# Front_left_lamp_v2.net
KiCad netlist of a schematic drawn in EAGLE
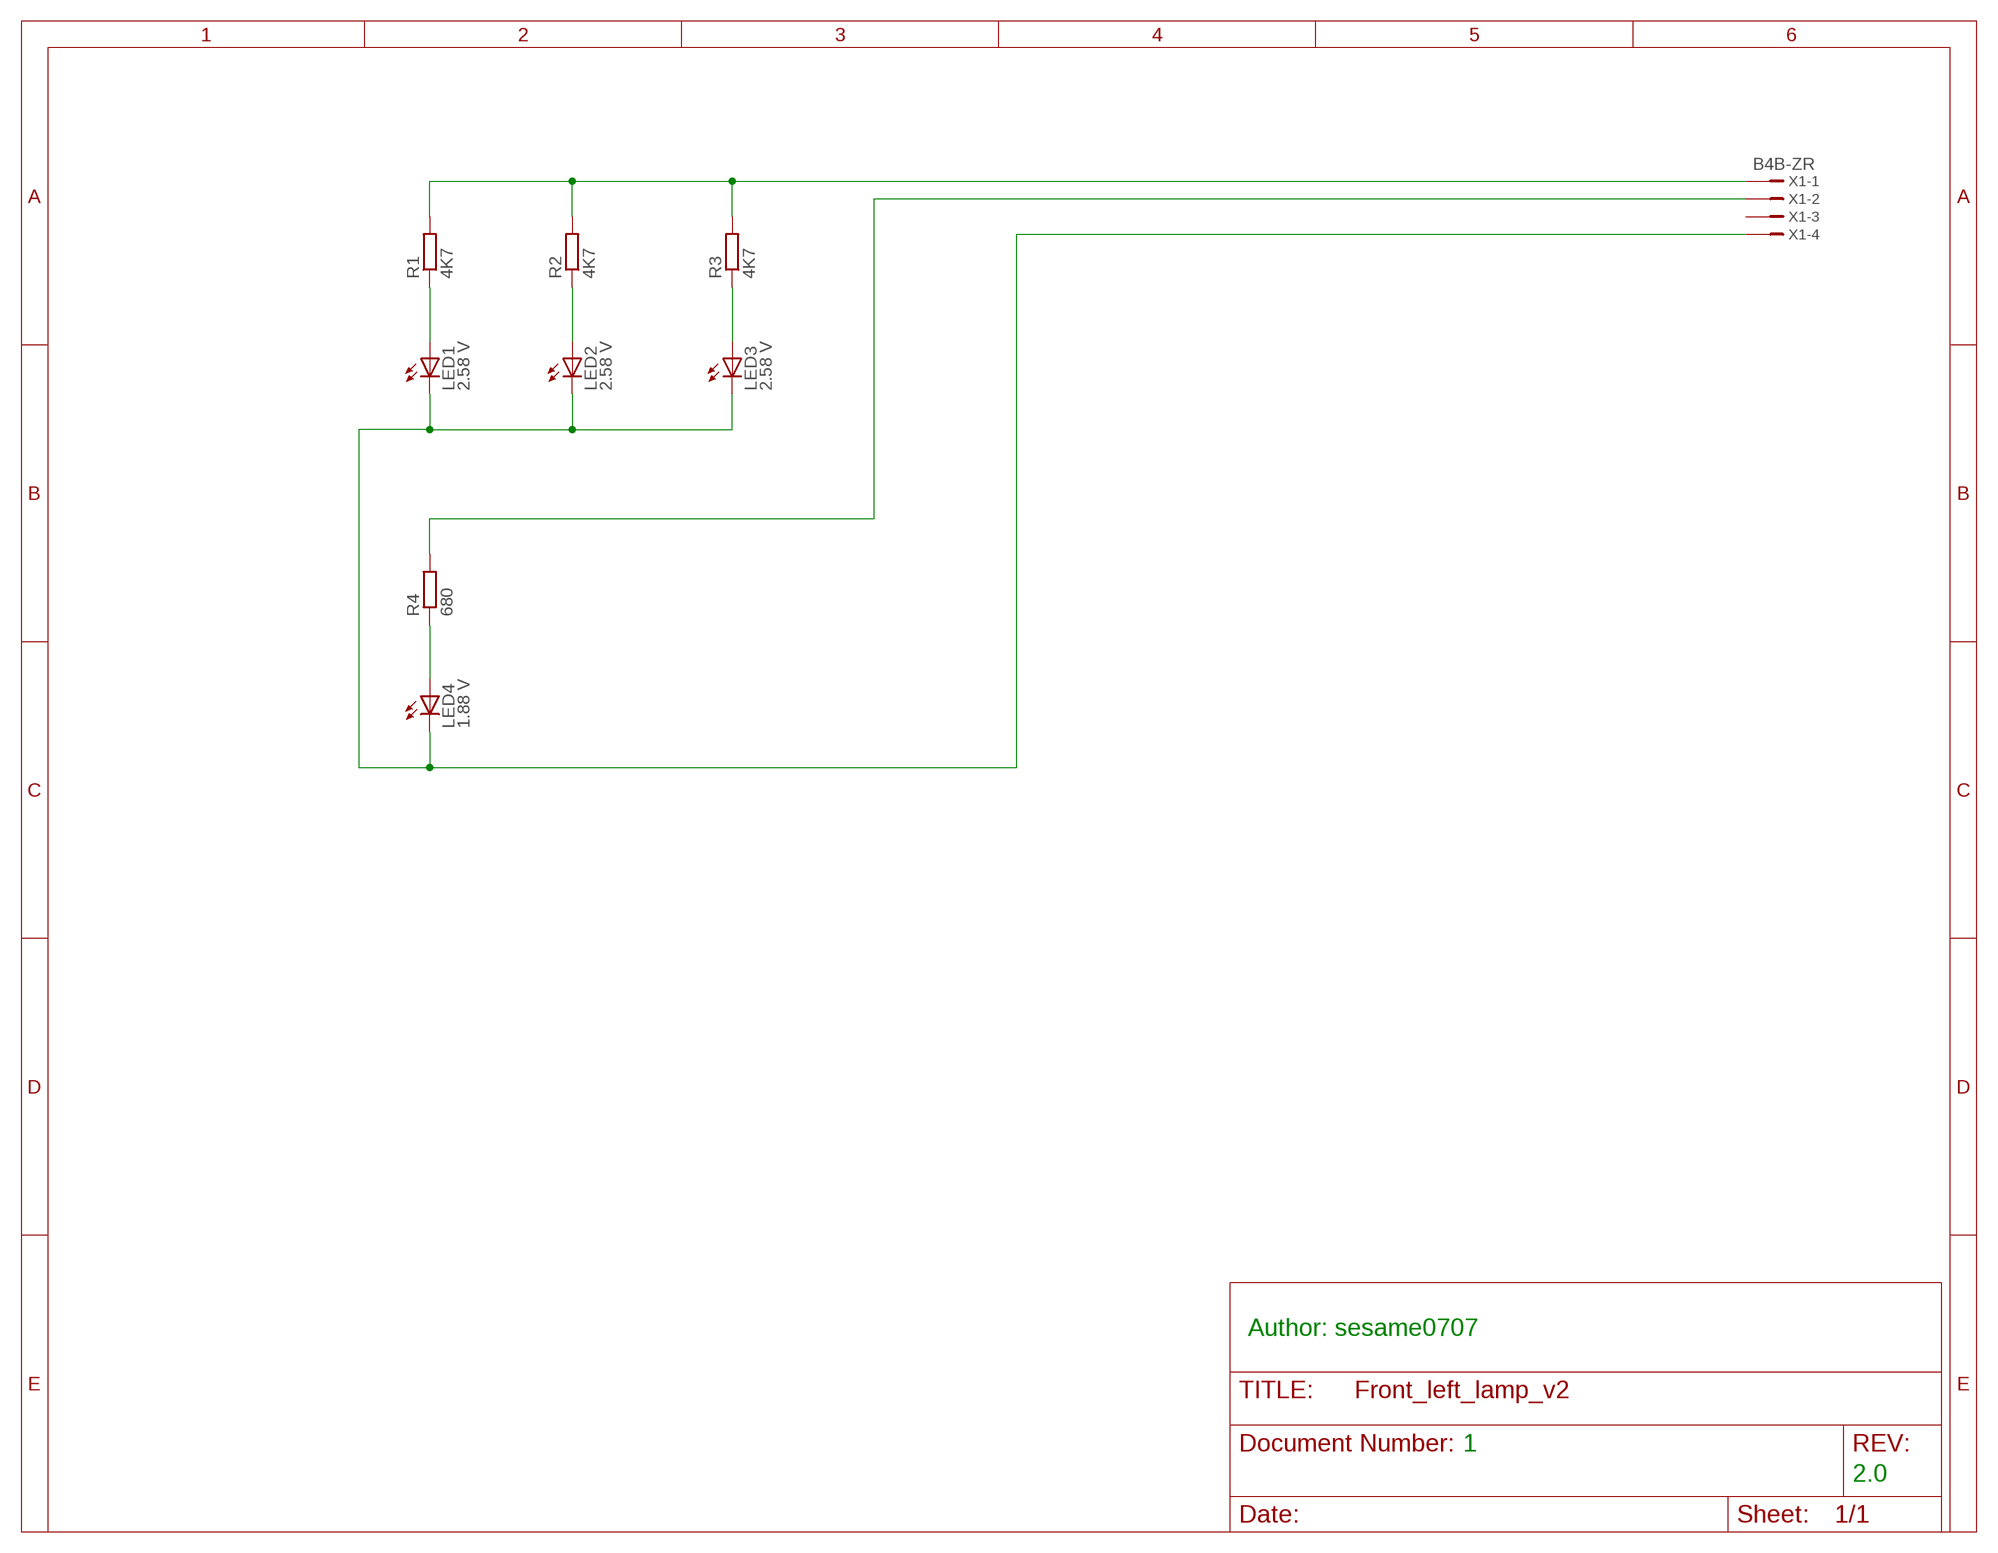
[diagram p0: schematic, sheet 1]

(export (version "E")
  (design (tool "Eeschema 10.0.6"))
  (components
    (comp (ref "LED1")
      (value "2.58 V")
      (footprint "eagle-import:LED5MM")
      (libsource (lib "eagle-import") (part "LED5MM"))
    )
    (comp (ref "LED2")
      (value "2.58 V")
      (footprint "eagle-import:LED5MM")
      (libsource (lib "eagle-import") (part "LED5MM"))
    )
    (comp (ref "LED3")
      (value "2.58 V")
      (footprint "eagle-import:LED5MM")
      (libsource (lib "eagle-import") (part "LED5MM"))
    )
    (comp (ref "LED4")
      (value "1.88 V")
      (footprint "eagle-import:LED5MM")
      (libsource (lib "eagle-import") (part "LED5MM"))
    )
    (comp (ref "R1")
      (value "4K7")
      (footprint "eagle-import:0204V")
      (libsource (lib "eagle-import") (part "R-EU_0204/2V"))
    )
    (comp (ref "R2")
      (value "4K7")
      (footprint "eagle-import:0204V")
      (libsource (lib "eagle-import") (part "R-EU_0204/2V"))
    )
    (comp (ref "R3")
      (value "4K7")
      (footprint "eagle-import:0204V")
      (libsource (lib "eagle-import") (part "R-EU_0204/2V"))
    )
    (comp (ref "R4")
      (value "680")
      (footprint "eagle-import:0204V")
      (libsource (lib "eagle-import") (part "R-EU_0204/2V"))
    )
    (comp (ref "X1")
      (value "B4B-ZR")
      (footprint "eagle-import:B4B-ZR")
      (fields (field (name "MF") "FARNELL") (field (name "MPN") "B4B-ZR(LF)(SN)"))
      (libsource (lib "eagle-import") (part "?4B-ZRB"))
    )
  )
  (nets
    (net (code "1") (name "Net-(LED1-C)") (class "Default")
      (node (ref "LED1") (pin "K") (pinfunction "C_K") (pintype "passive"))
      (node (ref "LED2") (pin "K") (pinfunction "C_K") (pintype "passive"))
      (node (ref "LED3") (pin "K") (pinfunction "C_K") (pintype "passive"))
      (node (ref "LED4") (pin "K") (pinfunction "C_K") (pintype "passive"))
      (node (ref "X1") (pin "4") (pinfunction "1_4") (pintype "passive"))
    )
    (net (code "2") (name "Net-(LED1-PadA)") (class "Default")
      (node (ref "LED1") (pin "A") (pinfunction "A_A") (pintype "passive"))
      (node (ref "R1") (pin "1") (pinfunction "1_1") (pintype "passive"))
    )
    (net (code "3") (name "Net-(LED2-PadA)") (class "Default")
      (node (ref "LED2") (pin "A") (pinfunction "A_A") (pintype "passive"))
      (node (ref "R2") (pin "1") (pinfunction "1_1") (pintype "passive"))
    )
    (net (code "4") (name "Net-(LED3-PadA)") (class "Default")
      (node (ref "LED3") (pin "A") (pinfunction "A_A") (pintype "passive"))
      (node (ref "R3") (pin "1") (pinfunction "1_1") (pintype "passive"))
    )
    (net (code "5") (name "Net-(LED4-PadA)") (class "Default")
      (node (ref "LED4") (pin "A") (pinfunction "A_A") (pintype "passive"))
      (node (ref "R4") (pin "1") (pinfunction "1_1") (pintype "passive"))
    )
    (net (code "6") (name "Net-(R1-Pad2)") (class "Default")
      (node (ref "R1") (pin "2") (pinfunction "2_2") (pintype "passive"))
      (node (ref "R2") (pin "2") (pinfunction "2_2") (pintype "passive"))
      (node (ref "R3") (pin "2") (pinfunction "2_2") (pintype "passive"))
      (node (ref "X1") (pin "1") (pinfunction "1_1") (pintype "passive"))
    )
    (net (code "7") (name "Net-(X1B-1)") (class "Default")
      (node (ref "R4") (pin "2") (pinfunction "2_2") (pintype "passive"))
      (node (ref "X1") (pin "2") (pinfunction "1_2") (pintype "passive"))
    )
    (net (code "8") (name "unconnected-(X1C-1-Pad3)") (class "Default")
      (node (ref "X1") (pin "3") (pinfunction "1_3") (pintype "passive"))
    )
  )
)
